# ABIMC_Board.net
KiCad netlist of a schematic drawn in EAGLE
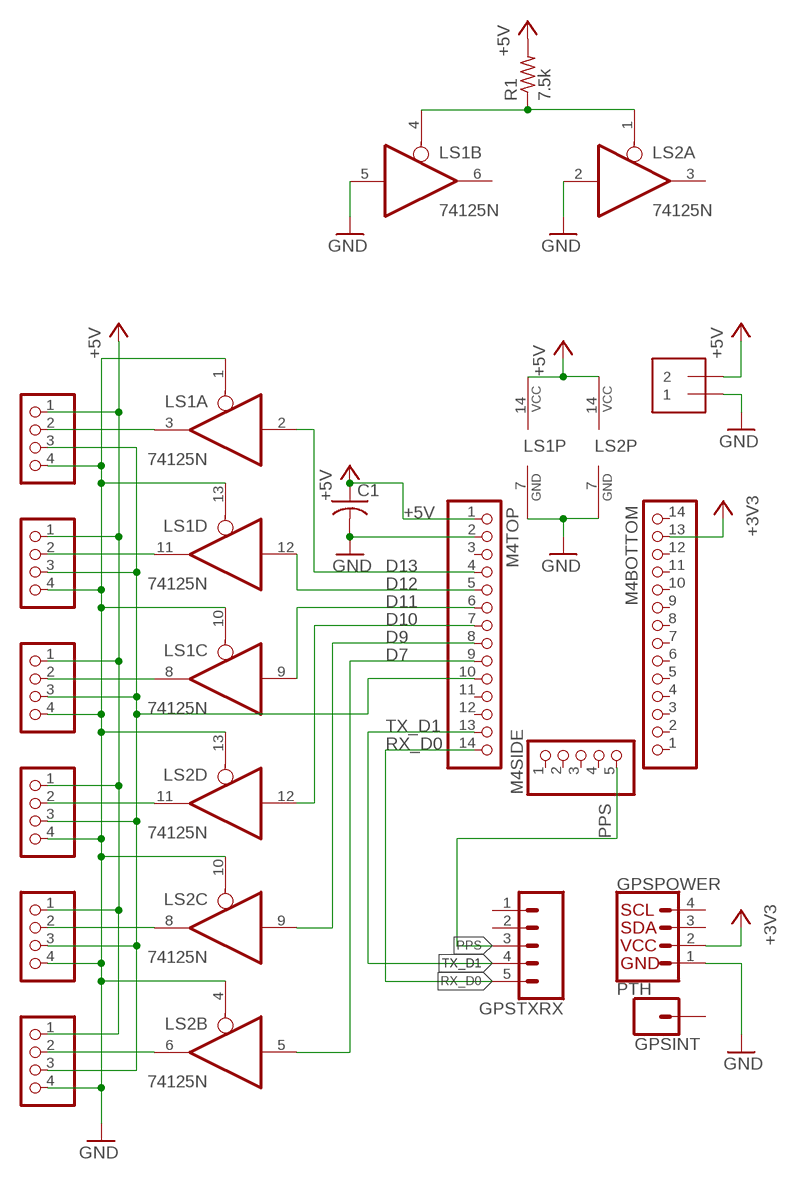
[diagram p0: schematic, sheet 1]

(export (version "E")
  (design (tool "Eeschema 10.0.6"))
  (components
    (comp (ref "C1")
      (value "C-US050-024X044")
      (footprint "eagle-import:C050-024X044")
      (libsource (lib "eagle-import") (part "C-US050-024X044"))
    )
    (comp (ref "GPSINT")
      (value "CONN_01PTH_NO_SILK_YES_STOP")
      (footprint "eagle-import:1X01_NO_SILK")
      (fields (field (name "SPICEPREFIX") "X"))
      (libsource (lib "eagle-import") (part "CONN_01PTH_NO_SILK_YES_STOP"))
    )
    (comp (ref "GPSPOWER")
      (value "PTH")
      (footprint "eagle-import:1X04_NO_SILK")
      (fields (field (name "SPICEPREFIX") "E"))
      (libsource (lib "eagle-import") (part "I2C_STANDARD_NO_SILK"))
    )
    (comp (ref "GPSTXRX")
      (value "CONN_05NO_SILK")
      (footprint "eagle-import:1X05_NO_SILK")
      (fields (field (name "SPICEPREFIX") "X"))
      (libsource (lib "eagle-import") (part "CONN_05NO_SILK"))
    )
    (comp (ref "JP1")
      (value "PINHD-1X4/90")
      (footprint "eagle-import:1X04_90")
      (libsource (lib "eagle-import") (part "PINHD-1X4/90"))
    )
    (comp (ref "JP2")
      (value "PINHD-1X4/90")
      (footprint "eagle-import:1X04_90")
      (libsource (lib "eagle-import") (part "PINHD-1X4/90"))
    )
    (comp (ref "JP3")
      (value "PINHD-1X4/90")
      (footprint "eagle-import:1X04_90")
      (libsource (lib "eagle-import") (part "PINHD-1X4/90"))
    )
    (comp (ref "JP4")
      (value "PINHD-1X4/90")
      (footprint "eagle-import:1X04_90")
      (libsource (lib "eagle-import") (part "PINHD-1X4/90"))
    )
    (comp (ref "JP5")
      (value "PINHD-1X4/90")
      (footprint "eagle-import:1X04_90")
      (libsource (lib "eagle-import") (part "PINHD-1X4/90"))
    )
    (comp (ref "JP6")
      (value "PINHD-1X4/90")
      (footprint "eagle-import:1X04_90")
      (libsource (lib "eagle-import") (part "PINHD-1X4/90"))
    )
    (comp (ref "LS1")
      (value "74125N")
      (footprint "eagle-import:DIL14")
      (libsource (lib "eagle-import") (part "74125N"))
    )
    (comp (ref "LS2")
      (value "74125N")
      (footprint "eagle-import:DIL14")
      (libsource (lib "eagle-import") (part "74125N"))
    )
    (comp (ref "M4BOTTOM")
      (value "HEADER-1X14")
      (footprint "eagle-import:1X14_ROUND70")
      (fields (field (name "SPICEPREFIX") "X"))
      (libsource (lib "eagle-import") (part "HEADER-1X14"))
    )
    (comp (ref "M4SIDE")
      (value "HEADER-1X570MIL")
      (footprint "eagle-import:1X05_ROUND_70")
      (fields (field (name "SPICEPREFIX") "X"))
      (libsource (lib "eagle-import") (part "HEADER-1X570MIL"))
    )
    (comp (ref "M4TOP")
      (value "HEADER-1X14")
      (footprint "eagle-import:1X14_ROUND70")
      (fields (field (name "SPICEPREFIX") "X"))
      (libsource (lib "eagle-import") (part "HEADER-1X14"))
    )
    (comp (ref "POWER")
      (value "1X2-3.5MM")
      (footprint "eagle-import:1X2-3.5MM")
      (fields (field (name "SPICEPREFIX") "B"))
      (libsource (lib "eagle-import") (part "1X2-3.5MM"))
    )
    (comp (ref "R1")
      (value "7.5k")
      (footprint "eagle-import:0204_7")
      (libsource (lib "eagle-import") (part "R-US_0204/7"))
    )
  )
  (nets
    (net (code "1") (name "+3V3") (class "Default")
      (node (ref "GPSPOWER") (pin "2") (pinfunction "VCC_2") (pintype "power_in"))
      (node (ref "M4BOTTOM") (pin "13") (pinfunction "13_13") (pintype "passive"))
    )
    (net (code "2") (name "+5V") (class "Default")
      (node (ref "C1") (pin "1") (pinfunction "1_1") (pintype "passive"))
      (node (ref "JP1") (pin "1") (pinfunction "1_1") (pintype "passive"))
      (node (ref "JP2") (pin "1") (pinfunction "1_1") (pintype "passive"))
      (node (ref "JP3") (pin "1") (pinfunction "1_1") (pintype "passive"))
      (node (ref "JP4") (pin "1") (pinfunction "1_1") (pintype "passive"))
      (node (ref "JP5") (pin "1") (pinfunction "1_1") (pintype "passive"))
      (node (ref "JP6") (pin "1") (pinfunction "1_1") (pintype "passive"))
      (node (ref "LS1") (pin "14") (pinfunction "VCC_14") (pintype "power_in"))
      (node (ref "LS2") (pin "14") (pinfunction "VCC_14") (pintype "power_in"))
      (node (ref "M4TOP") (pin "1") (pinfunction "1_1") (pintype "passive"))
      (node (ref "POWER") (pin "2") (pinfunction "2_2") (pintype "passive"))
      (node (ref "R1") (pin "2") (pinfunction "2_2") (pintype "passive"))
    )
    (net (code "3") (name "/D7") (class "Default")
      (node (ref "LS2") (pin "5") (pinfunction "I_5") (pintype "input"))
      (node (ref "M4TOP") (pin "9") (pinfunction "9_9") (pintype "passive"))
    )
    (net (code "4") (name "/D9") (class "Default")
      (node (ref "LS2") (pin "9") (pinfunction "I_9") (pintype "input"))
      (node (ref "M4TOP") (pin "8") (pinfunction "8_8") (pintype "passive"))
    )
    (net (code "5") (name "/D10") (class "Default")
      (node (ref "LS2") (pin "12") (pinfunction "I_12") (pintype "input"))
      (node (ref "M4TOP") (pin "7") (pinfunction "7_7") (pintype "passive"))
    )
    (net (code "6") (name "/D11") (class "Default")
      (node (ref "LS1") (pin "9") (pinfunction "I_9") (pintype "input"))
      (node (ref "M4TOP") (pin "6") (pinfunction "6_6") (pintype "passive"))
    )
    (net (code "7") (name "/D12") (class "Default")
      (node (ref "LS1") (pin "12") (pinfunction "I_12") (pintype "input"))
      (node (ref "M4TOP") (pin "5") (pinfunction "5_5") (pintype "passive"))
    )
    (net (code "8") (name "/D13") (class "Default")
      (node (ref "LS1") (pin "2") (pinfunction "I_2") (pintype "input"))
      (node (ref "M4TOP") (pin "4") (pinfunction "4_4") (pintype "passive"))
    )
    (net (code "9") (name "GND") (class "Default")
      (node (ref "C1") (pin "2") (pinfunction "2_2") (pintype "passive"))
      (node (ref "GPSPOWER") (pin "1") (pinfunction "GND_1") (pintype "power_in"))
      (node (ref "JP1") (pin "4") (pinfunction "4_4") (pintype "passive"))
      (node (ref "JP2") (pin "4") (pinfunction "4_4") (pintype "passive"))
      (node (ref "JP3") (pin "4") (pinfunction "4_4") (pintype "passive"))
      (node (ref "JP4") (pin "4") (pinfunction "4_4") (pintype "passive"))
      (node (ref "JP5") (pin "4") (pinfunction "4_4") (pintype "passive"))
      (node (ref "JP6") (pin "4") (pinfunction "4_4") (pintype "passive"))
      (node (ref "LS1") (pin "1") (pinfunction "OE_1") (pintype "input"))
      (node (ref "LS1") (pin "10") (pinfunction "OE_10") (pintype "input"))
      (node (ref "LS1") (pin "13") (pinfunction "OE_13") (pintype "input"))
      (node (ref "LS1") (pin "5") (pinfunction "I_5") (pintype "input"))
      (node (ref "LS1") (pin "7") (pinfunction "GND_7") (pintype "power_in"))
      (node (ref "LS2") (pin "10") (pinfunction "OE_10") (pintype "input"))
      (node (ref "LS2") (pin "13") (pinfunction "OE_13") (pintype "input"))
      (node (ref "LS2") (pin "2") (pinfunction "I_2") (pintype "input"))
      (node (ref "LS2") (pin "4") (pinfunction "OE_4") (pintype "input"))
      (node (ref "LS2") (pin "7") (pinfunction "GND_7") (pintype "power_in"))
      (node (ref "M4TOP") (pin "2") (pinfunction "2_2") (pintype "passive"))
      (node (ref "POWER") (pin "1") (pinfunction "1_1") (pintype "passive"))
    )
    (net (code "10") (name "Net-(JP1-Pad3)") (class "Default")
      (node (ref "JP1") (pin "3") (pinfunction "3_3") (pintype "passive"))
      (node (ref "JP2") (pin "3") (pinfunction "3_3") (pintype "passive"))
      (node (ref "JP3") (pin "3") (pinfunction "3_3") (pintype "passive"))
      (node (ref "JP4") (pin "3") (pinfunction "3_3") (pintype "passive"))
      (node (ref "JP5") (pin "3") (pinfunction "3_3") (pintype "passive"))
      (node (ref "JP6") (pin "3") (pinfunction "3_3") (pintype "passive"))
      (node (ref "M4TOP") (pin "10") (pinfunction "10_10") (pintype "passive"))
    )
    (net (code "11") (name "Net-(LS1A-O)") (class "Default")
      (node (ref "JP1") (pin "2") (pinfunction "2_2") (pintype "passive"))
      (node (ref "LS1") (pin "3") (pinfunction "O_3") (pintype "tri_state"))
    )
    (net (code "12") (name "Net-(LS1B-OE)") (class "Default")
      (node (ref "LS1") (pin "4") (pinfunction "OE_4") (pintype "input"))
      (node (ref "LS2") (pin "1") (pinfunction "OE_1") (pintype "input"))
      (node (ref "R1") (pin "1") (pinfunction "1_1") (pintype "passive"))
    )
    (net (code "13") (name "Net-(LS1C-O)") (class "Default")
      (node (ref "JP3") (pin "2") (pinfunction "2_2") (pintype "passive"))
      (node (ref "LS1") (pin "8") (pinfunction "O_8") (pintype "tri_state"))
    )
    (net (code "14") (name "Net-(LS1D-O)") (class "Default")
      (node (ref "JP2") (pin "2") (pinfunction "2_2") (pintype "passive"))
      (node (ref "LS1") (pin "11") (pinfunction "O_11") (pintype "tri_state"))
    )
    (net (code "15") (name "Net-(LS2B-O)") (class "Default")
      (node (ref "JP6") (pin "2") (pinfunction "2_2") (pintype "passive"))
      (node (ref "LS2") (pin "6") (pinfunction "O_6") (pintype "tri_state"))
    )
    (net (code "16") (name "Net-(LS2C-O)") (class "Default")
      (node (ref "JP5") (pin "2") (pinfunction "2_2") (pintype "passive"))
      (node (ref "LS2") (pin "8") (pinfunction "O_8") (pintype "tri_state"))
    )
    (net (code "17") (name "Net-(LS2D-O)") (class "Default")
      (node (ref "JP4") (pin "2") (pinfunction "2_2") (pintype "passive"))
      (node (ref "LS2") (pin "11") (pinfunction "O_11") (pintype "tri_state"))
    )
    (net (code "18") (name "PPS") (class "Default")
      (node (ref "GPSTXRX") (pin "3") (pinfunction "3_3") (pintype "passive"))
      (node (ref "M4SIDE") (pin "5") (pinfunction "5_5") (pintype "passive"))
    )
    (net (code "19") (name "RX_D0") (class "Default")
      (node (ref "GPSTXRX") (pin "5") (pinfunction "5_5") (pintype "passive"))
      (node (ref "M4TOP") (pin "14") (pinfunction "14_14") (pintype "passive"))
    )
    (net (code "20") (name "TX_D1") (class "Default")
      (node (ref "GPSTXRX") (pin "4") (pinfunction "4_4") (pintype "passive"))
      (node (ref "M4TOP") (pin "13") (pinfunction "13_13") (pintype "passive"))
    )
    (net (code "21") (name "unconnected-(GPSINT-Pad1)") (class "Default")
      (node (ref "GPSINT") (pin "1") (pinfunction "1_1") (pintype "passive"))
    )
    (net (code "22") (name "unconnected-(GPSPOWER-SCL-Pad4)") (class "Default")
      (node (ref "GPSPOWER") (pin "4") (pinfunction "SCL_4") (pintype "passive"))
    )
    (net (code "23") (name "unconnected-(GPSPOWER-SDA-Pad3)") (class "Default")
      (node (ref "GPSPOWER") (pin "3") (pinfunction "SDA_3") (pintype "passive"))
    )
    (net (code "24") (name "unconnected-(GPSTXRX-Pad1)") (class "Default")
      (node (ref "GPSTXRX") (pin "1") (pinfunction "1_1") (pintype "passive"))
    )
    (net (code "25") (name "unconnected-(GPSTXRX-Pad2)") (class "Default")
      (node (ref "GPSTXRX") (pin "2") (pinfunction "2_2") (pintype "passive"))
    )
    (net (code "26") (name "unconnected-(LS1B-O-Pad6)") (class "Default")
      (node (ref "LS1") (pin "6") (pinfunction "O_6") (pintype "tri_state"))
    )
    (net (code "27") (name "unconnected-(LS2A-O-Pad3)") (class "Default")
      (node (ref "LS2") (pin "3") (pinfunction "O_3") (pintype "tri_state"))
    )
    (net (code "28") (name "unconnected-(M4BOTTOM-Pad1)") (class "Default")
      (node (ref "M4BOTTOM") (pin "1") (pinfunction "1_1") (pintype "passive"))
    )
    (net (code "29") (name "unconnected-(M4BOTTOM-Pad2)") (class "Default")
      (node (ref "M4BOTTOM") (pin "2") (pinfunction "2_2") (pintype "passive"))
    )
    (net (code "30") (name "unconnected-(M4BOTTOM-Pad3)") (class "Default")
      (node (ref "M4BOTTOM") (pin "3") (pinfunction "3_3") (pintype "passive"))
    )
    (net (code "31") (name "unconnected-(M4BOTTOM-Pad4)") (class "Default")
      (node (ref "M4BOTTOM") (pin "4") (pinfunction "4_4") (pintype "passive"))
    )
    (net (code "32") (name "unconnected-(M4BOTTOM-Pad5)") (class "Default")
      (node (ref "M4BOTTOM") (pin "5") (pinfunction "5_5") (pintype "passive"))
    )
    (net (code "33") (name "unconnected-(M4BOTTOM-Pad6)") (class "Default")
      (node (ref "M4BOTTOM") (pin "6") (pinfunction "6_6") (pintype "passive"))
    )
    (net (code "34") (name "unconnected-(M4BOTTOM-Pad7)") (class "Default")
      (node (ref "M4BOTTOM") (pin "7") (pinfunction "7_7") (pintype "passive"))
    )
    (net (code "35") (name "unconnected-(M4BOTTOM-Pad8)") (class "Default")
      (node (ref "M4BOTTOM") (pin "8") (pinfunction "8_8") (pintype "passive"))
    )
    (net (code "36") (name "unconnected-(M4BOTTOM-Pad9)") (class "Default")
      (node (ref "M4BOTTOM") (pin "9") (pinfunction "9_9") (pintype "passive"))
    )
    (net (code "37") (name "unconnected-(M4BOTTOM-Pad10)") (class "Default")
      (node (ref "M4BOTTOM") (pin "10") (pinfunction "10_10") (pintype "passive"))
    )
    (net (code "38") (name "unconnected-(M4BOTTOM-Pad11)") (class "Default")
      (node (ref "M4BOTTOM") (pin "11") (pinfunction "11_11") (pintype "passive"))
    )
    (net (code "39") (name "unconnected-(M4BOTTOM-Pad12)") (class "Default")
      (node (ref "M4BOTTOM") (pin "12") (pinfunction "12_12") (pintype "passive"))
    )
    (net (code "40") (name "unconnected-(M4BOTTOM-Pad14)") (class "Default")
      (node (ref "M4BOTTOM") (pin "14") (pinfunction "14_14") (pintype "passive"))
    )
    (net (code "41") (name "unconnected-(M4SIDE-Pad1)") (class "Default")
      (node (ref "M4SIDE") (pin "1") (pinfunction "1_1") (pintype "passive"))
    )
    (net (code "42") (name "unconnected-(M4SIDE-Pad2)") (class "Default")
      (node (ref "M4SIDE") (pin "2") (pinfunction "2_2") (pintype "passive"))
    )
    (net (code "43") (name "unconnected-(M4SIDE-Pad3)") (class "Default")
      (node (ref "M4SIDE") (pin "3") (pinfunction "3_3") (pintype "passive"))
    )
    (net (code "44") (name "unconnected-(M4SIDE-Pad4)") (class "Default")
      (node (ref "M4SIDE") (pin "4") (pinfunction "4_4") (pintype "passive"))
    )
    (net (code "45") (name "unconnected-(M4TOP-Pad3)") (class "Default")
      (node (ref "M4TOP") (pin "3") (pinfunction "3_3") (pintype "passive"))
    )
    (net (code "46") (name "unconnected-(M4TOP-Pad11)") (class "Default")
      (node (ref "M4TOP") (pin "11") (pinfunction "11_11") (pintype "passive"))
    )
    (net (code "47") (name "unconnected-(M4TOP-Pad12)") (class "Default")
      (node (ref "M4TOP") (pin "12") (pinfunction "12_12") (pintype "passive"))
    )
  )
)
